# Sheet3.net
KiCad netlist of a schematic drawn in Altium Designer
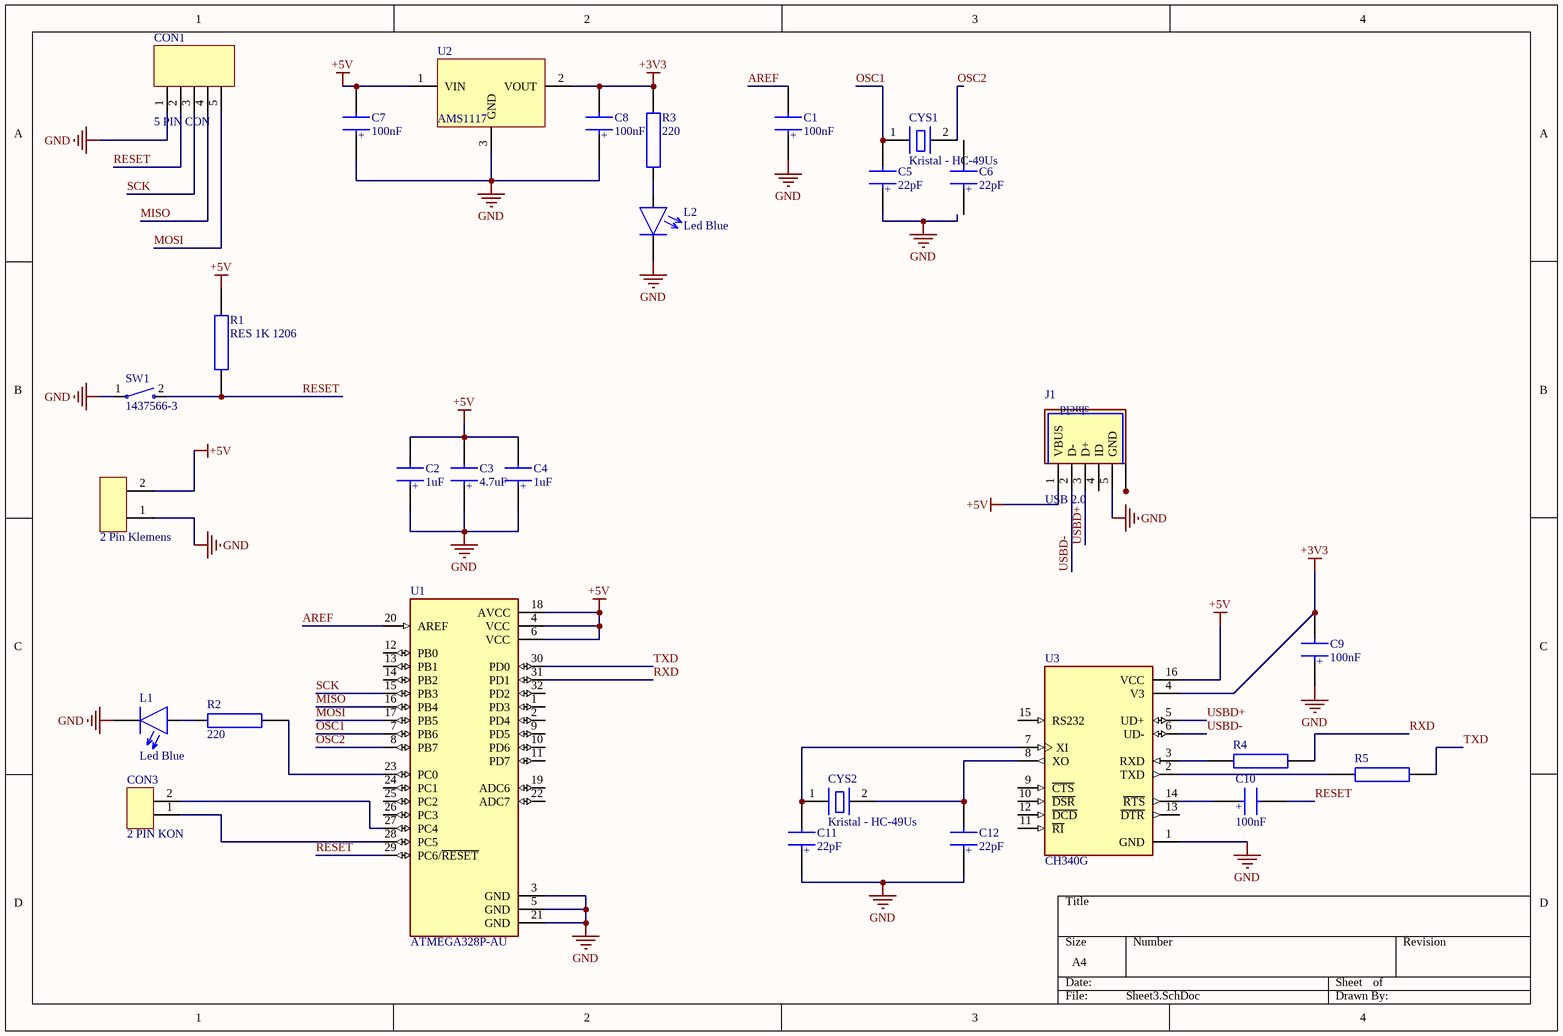
[diagram p0: Sheet3.SchDoc]

(export (version "E")
  (design (tool "Eeschema 10.0.6"))
  (components
    (comp (ref "C1")
      (value "100nF")
      (footprint "CAP_805")
      (description "0805 smd")
      (libsource (lib "Udemy_Schlib1") (part "CAP 22uf 0805"))
    )
    (comp (ref "C2")
      (value "1uF")
      (footprint "CAP_805")
      (description "0805 smd")
      (libsource (lib "Udemy_Schlib1") (part "CAP 22uf 0805"))
    )
    (comp (ref "C3")
      (value "4.7uF")
      (footprint "CAP_805")
      (description "0805 smd")
      (libsource (lib "Udemy_Schlib1") (part "CAP 22uf 0805"))
    )
    (comp (ref "C4")
      (value "1uF")
      (footprint "CAP_805")
      (description "0805 smd")
      (libsource (lib "Udemy_Schlib1") (part "CAP 22uf 0805"))
    )
    (comp (ref "C5")
      (value "22pF")
      (footprint "CAP_805")
      (description "0805 smd")
      (libsource (lib "Udemy_Schlib1") (part "CAP 22uf 0805"))
    )
    (comp (ref "C6")
      (value "22pF")
      (footprint "CAP_805")
      (description "0805 smd")
      (libsource (lib "Udemy_Schlib1") (part "CAP 22uf 0805"))
    )
    (comp (ref "C7")
      (value "100nF")
      (footprint "CAP_805")
      (description "0805 smd")
      (libsource (lib "Udemy_Schlib1") (part "CAP 22uf 0805"))
    )
    (comp (ref "C8")
      (value "100nF")
      (footprint "CAP_805")
      (description "0805 smd")
      (libsource (lib "Udemy_Schlib1") (part "CAP 22uf 0805"))
    )
    (comp (ref "C9")
      (value "100nF")
      (footprint "CAP_805")
      (description "0805 smd")
      (libsource (lib "Udemy_Schlib1") (part "CAP 22uf 0805"))
    )
    (comp (ref "C10")
      (value "100nF")
      (footprint "CAP_805")
      (description "0805 smd")
      (libsource (lib "Udemy_Schlib1") (part "CAP 22uf 0805"))
    )
    (comp (ref "C11")
      (value "22pF")
      (footprint "CAP_805")
      (description "0805 smd")
      (libsource (lib "Udemy_Schlib1") (part "CAP 22uf 0805"))
    )
    (comp (ref "C12")
      (value "22pF")
      (footprint "CAP_805")
      (description "0805 smd")
      (libsource (lib "Udemy_Schlib1") (part "CAP 22uf 0805"))
    )
    (comp (ref "CON1")
      (value "5 PIN CON")
      (footprint "5 PIN 2.54MM")
      (description "2.54mm vertical connector")
      (libsource (lib "Udemy_Schlib1") (part "5 PIN CON"))
    )
    (comp (ref "CON3")
      (value "2 PIN KON")
      (footprint "2 PIN 2.54MM")
      (description "2.54 mm vertical")
      (libsource (lib "Udemy_Schlib1") (part "2 PIN KON"))
    )
    (comp (ref "CYS1")
      (value "Kristal - HC-49Us")
      (footprint "Kristal - HC-49Us -smd")
      (description "Smd tipi kristal")
      (libsource (lib "Udemy_Schlib1") (part "Kristal - HC-49Us"))
    )
    (comp (ref "CYS2")
      (value "Kristal - HC-49Us")
      (footprint "Kristal - HC-49Us -smd")
      (description "Smd tipi kristal")
      (libsource (lib "Udemy_Schlib1") (part "Kristal - HC-49Us"))
    )
    (comp (ref "J1")
      (value "USB 2.0")
      (footprint "65100516121")
      (description "USB - mini B USB 2.0 Receptacle Connector 5 Position Surface Mount, Right Angle")
      (fields (field (name "MP") "65100516121") (field (name "MF") "WÃ¼rth Elektronik"))
      (libsource (lib "Schlib") (part "USB 2.0"))
    )
    (comp (ref "KLM1")
      (value "2 Pin Klemens")
      (footprint "5.08mm-2 pin")
      (description "5.08mm 2 pin klemens")
      (libsource (lib "Udemy_Schlib1") (part "2 Pin Klemens"))
    )
    (comp (ref "L1")
      (value "Led Blue")
      (footprint "Led 1206")
      (libsource (lib "Udemy_Schlib1") (part "Led Blue"))
    )
    (comp (ref "L2")
      (value "Led Blue")
      (footprint "Led 1206")
      (libsource (lib "Udemy_Schlib1") (part "Led Blue"))
    )
    (comp (ref "R1")
      (value "RES 1K 1206")
      (footprint "RES_1206")
      (libsource (lib "Udemy_Schlib1") (part "RES 1K 1206"))
    )
    (comp (ref "R2")
      (value "220")
      (footprint "RES_1206")
      (libsource (lib "Udemy_Schlib1") (part "RES 1K 1206"))
    )
    (comp (ref "R3")
      (value "220")
      (footprint "RES_1206")
      (libsource (lib "Udemy_Schlib1") (part "RES 1K 1206"))
    )
    (comp (ref "R4")
      (value "RES 1K 1206")
      (footprint "RES_1206")
      (libsource (lib "Udemy_Schlib1") (part "RES 1K 1206"))
    )
    (comp (ref "R5")
      (value "RES 1K 1206")
      (footprint "RES_1206")
      (libsource (lib "Udemy_Schlib1") (part "RES 1K 1206"))
    )
    (comp (ref "SW1")
      (value "1437566-3")
      (footprint "SW_1437566-3")
      (description "Switch Tactile OFF (ON) SPST Rectangular Button Gull Wing 0.05A 12VDC SMD Loose Piece")
      (libsource (lib "Schlib") (part "1437566-3"))
    )
    (comp (ref "U1")
      (value "ATMEGA328P-AU")
      (footprint "QFP80P900X900X120-32N")
      (description "AVR AVRÂ® ATmega Microcontroller IC 8-Bit 20MHz 32KB (16K x 16) FLASH 32-TQFP (7x7)")
      (fields (field (name "MF") "Microchip Technology"))
      (libsource (lib "Schlib") (part "ATMEGA328P-AU"))
    )
    (comp (ref "U2")
      (value "AMS1117")
      (footprint "AMS1117")
      (description "3V3 Voltage Regulator")
      (libsource (lib "Udemy_Schlib1") (part "AMS1117"))
    )
    (comp (ref "U3")
      (value "CH340G")
      (footprint "SOIC127P600X180-16N")
      (description "USB Interface Integrated Circuit")
      (fields (field (name "MP") "Ch340G") (field (name "MF") "WCH"))
      (libsource (lib "Schlib") (part "CH340G"))
    )
  )
  (nets
    (net (code "1") (name "+3V3") (class "Default")
      (node (ref "C8") (pin "2") (pinfunction "2_2") (pintype "passive"))
      (node (ref "C9") (pin "2") (pinfunction "2_2") (pintype "passive"))
      (node (ref "R3") (pin "2") (pintype "passive"))
      (node (ref "U2") (pin "2") (pinfunction "VOUT_2") (pintype "passive"))
      (node (ref "U3") (pin "4") (pinfunction "V3_4") (pintype "power_in"))
    )
    (net (code "2") (name "+5V") (class "Default")
      (node (ref "C2") (pin "2") (pinfunction "2_2") (pintype "passive"))
      (node (ref "C3") (pin "2") (pinfunction "2_2") (pintype "passive"))
      (node (ref "C4") (pin "2") (pinfunction "2_2") (pintype "passive"))
      (node (ref "C7") (pin "2") (pinfunction "2_2") (pintype "passive"))
      (node (ref "J1") (pin "1") (pinfunction "VBUS_1") (pintype "passive"))
      (node (ref "KLM1") (pin "2") (pintype "passive"))
      (node (ref "R1") (pin "2") (pintype "passive"))
      (node (ref "U1") (pin "18") (pinfunction "AVCC_18") (pintype "power_in"))
      (node (ref "U1") (pin "4") (pinfunction "VCC_4") (pintype "power_in"))
      (node (ref "U1") (pin "6") (pinfunction "VCC_6") (pintype "power_in"))
      (node (ref "U2") (pin "1") (pinfunction "VIN_1") (pintype "passive"))
      (node (ref "U3") (pin "16") (pinfunction "VCC_16") (pintype "power_in"))
    )
    (net (code "3") (name "/AREF") (class "Default")
      (node (ref "C1") (pin "2") (pinfunction "2_2") (pintype "passive"))
      (node (ref "U1") (pin "20") (pinfunction "AREF_20") (pintype "input"))
    )
    (net (code "4") (name "/MISO") (class "Default")
      (node (ref "CON1") (pin "4") (pintype "passive"))
      (node (ref "U1") (pin "16") (pinfunction "PB4_16") (pintype "bidirectional"))
    )
    (net (code "5") (name "/MOSI") (class "Default")
      (node (ref "CON1") (pin "5") (pintype "passive"))
      (node (ref "U1") (pin "17") (pinfunction "PB5_17") (pintype "bidirectional"))
    )
    (net (code "6") (name "/OSC1") (class "Default")
      (node (ref "C5") (pin "2") (pinfunction "2_2") (pintype "passive"))
      (node (ref "CYS1") (pin "1") (pintype "passive"))
      (node (ref "U1") (pin "7") (pinfunction "PB6_7") (pintype "bidirectional"))
    )
    (net (code "7") (name "/OSC2") (class "Default")
      (node (ref "CYS1") (pin "2") (pintype "passive"))
      (node (ref "U1") (pin "8") (pinfunction "PB7_8") (pintype "bidirectional"))
    )
    (net (code "8") (name "/RESET") (class "Default")
      (node (ref "C10") (pin "2") (pinfunction "2_2") (pintype "passive"))
      (node (ref "CON1") (pin "2") (pintype "passive"))
      (node (ref "R1") (pin "1") (pintype "passive"))
      (node (ref "SW1") (pin "2") (pinfunction "2_2") (pintype "passive"))
      (node (ref "U1") (pin "29") (pinfunction "PC6/~{RESET}_29") (pintype "bidirectional"))
    )
    (net (code "9") (name "/RXD") (class "Default")
      (node (ref "R4") (pin "2") (pintype "passive"))
      (node (ref "U1") (pin "31") (pinfunction "PD1_31") (pintype "bidirectional"))
    )
    (net (code "10") (name "/SCK") (class "Default")
      (node (ref "CON1") (pin "3") (pintype "passive"))
      (node (ref "U1") (pin "15") (pinfunction "PB3_15") (pintype "bidirectional"))
    )
    (net (code "11") (name "/TXD") (class "Default")
      (node (ref "R5") (pin "2") (pintype "passive"))
      (node (ref "U1") (pin "30") (pinfunction "PD0_30") (pintype "bidirectional"))
    )
    (net (code "12") (name "/USBD+") (class "Default")
      (node (ref "J1") (pin "3") (pinfunction "D+_3") (pintype "passive"))
      (node (ref "U3") (pin "5") (pinfunction "UD+_5") (pintype "bidirectional"))
    )
    (net (code "13") (name "/USBD-") (class "Default")
      (node (ref "J1") (pin "2") (pinfunction "D-_2") (pintype "passive"))
      (node (ref "U3") (pin "6") (pinfunction "UD-_6") (pintype "bidirectional"))
    )
    (net (code "14") (name "GND") (class "Default")
      (node (ref "C1") (pin "1") (pinfunction "1_1") (pintype "passive"))
      (node (ref "C11") (pin "1") (pinfunction "1_1") (pintype "passive"))
      (node (ref "C12") (pin "1") (pinfunction "1_1") (pintype "passive"))
      (node (ref "C2") (pin "1") (pinfunction "1_1") (pintype "passive"))
      (node (ref "C3") (pin "1") (pinfunction "1_1") (pintype "passive"))
      (node (ref "C4") (pin "1") (pinfunction "1_1") (pintype "passive"))
      (node (ref "C5") (pin "1") (pinfunction "1_1") (pintype "passive"))
      (node (ref "C7") (pin "1") (pinfunction "1_1") (pintype "passive"))
      (node (ref "C8") (pin "1") (pinfunction "1_1") (pintype "passive"))
      (node (ref "C9") (pin "1") (pinfunction "1_1") (pintype "passive"))
      (node (ref "CON1") (pin "1") (pintype "passive"))
      (node (ref "J1") (pin "5") (pinfunction "GND_5") (pintype "passive"))
      (node (ref "KLM1") (pin "1") (pintype "passive"))
      (node (ref "L1") (pin "2") (pintype "passive"))
      (node (ref "L2") (pin "2") (pintype "passive"))
      (node (ref "SW1") (pin "1") (pinfunction "1_1") (pintype "passive"))
      (node (ref "U1") (pin "21") (pinfunction "GND_21") (pintype "power_in"))
      (node (ref "U1") (pin "3") (pinfunction "GND_3") (pintype "power_in"))
      (node (ref "U1") (pin "5") (pinfunction "GND_5") (pintype "power_in"))
      (node (ref "U2") (pin "3") (pinfunction "GND_3") (pintype "passive"))
      (node (ref "U3") (pin "1") (pinfunction "GND_1") (pintype "power_in"))
    )
    (net (code "15") (name "Net-(J1-SHIELD-PadS1)") (class "Default")
      (node (ref "J1") (pin "S1") (pinfunction "SHIELD_S1") (pintype "passive"))
      (node (ref "J1") (pin "S2") (pinfunction "SHIELD_S2") (pintype "passive"))
      (node (ref "J1") (pin "S3") (pinfunction "SHIELD_S3") (pintype "passive"))
      (node (ref "J1") (pin "S4") (pinfunction "SHIELD_S4") (pintype "passive"))
    )
    (net (code "16") (name "Net-(L1-Pad1)") (class "Default")
      (node (ref "L1") (pin "1") (pintype "passive"))
      (node (ref "R2") (pin "1") (pintype "passive"))
    )
    (net (code "17") (name "Net-(L2-Pad1)") (class "Default")
      (node (ref "L2") (pin "1") (pintype "passive"))
      (node (ref "R3") (pin "1") (pintype "passive"))
    )
    (net (code "18") (name "Net-(U1-PC0)") (class "Default")
      (node (ref "R2") (pin "2") (pintype "passive"))
      (node (ref "U1") (pin "23") (pinfunction "PC0_23") (pintype "bidirectional"))
    )
    (net (code "19") (name "Net-(U1-PC4)") (class "Default")
      (node (ref "CON3") (pin "2") (pintype "passive"))
      (node (ref "U1") (pin "27") (pinfunction "PC4_27") (pintype "bidirectional"))
    )
    (net (code "20") (name "Net-(U1-PC5)") (class "Default")
      (node (ref "CON3") (pin "1") (pintype "passive"))
      (node (ref "U1") (pin "28") (pinfunction "PC5_28") (pintype "bidirectional"))
    )
    (net (code "21") (name "Net-(U3-RXD)") (class "Default")
      (node (ref "R4") (pin "1") (pintype "passive"))
      (node (ref "U3") (pin "3") (pinfunction "RXD_3") (pintype "input"))
    )
    (net (code "22") (name "Net-(U3-TXD)") (class "Default")
      (node (ref "R5") (pin "1") (pintype "passive"))
      (node (ref "U3") (pin "2") (pinfunction "TXD_2") (pintype "output"))
    )
    (net (code "23") (name "Net-(U3-XI)") (class "Default")
      (node (ref "C11") (pin "2") (pinfunction "2_2") (pintype "passive"))
      (node (ref "CYS2") (pin "1") (pintype "passive"))
      (node (ref "U3") (pin "7") (pinfunction "XI_7") (pintype "input"))
    )
    (net (code "24") (name "Net-(U3-XO)") (class "Default")
      (node (ref "C12") (pin "2") (pinfunction "2_2") (pintype "passive"))
      (node (ref "CYS2") (pin "2") (pintype "passive"))
      (node (ref "U3") (pin "8") (pinfunction "XO_8") (pintype "output"))
    )
    (net (code "25") (name "Net-(U3-~{RTS})") (class "Default")
      (node (ref "C10") (pin "1") (pinfunction "1_1") (pintype "passive"))
      (node (ref "U3") (pin "14") (pinfunction "~{RTS}_14") (pintype "output"))
    )
    (net (code "26") (name "unconnected-(C6-Pad1)") (class "Default")
      (node (ref "C6") (pin "1") (pinfunction "1_1") (pintype "passive"))
    )
    (net (code "27") (name "unconnected-(C6-Pad2)") (class "Default")
      (node (ref "C6") (pin "2") (pinfunction "2_2") (pintype "passive"))
    )
    (net (code "28") (name "unconnected-(J1-ID-Pad4)") (class "Default")
      (node (ref "J1") (pin "4") (pinfunction "ID_4") (pintype "passive"))
    )
    (net (code "29") (name "unconnected-(U1-ADC6-Pad19)") (class "Default")
      (node (ref "U1") (pin "19") (pinfunction "ADC6_19") (pintype "bidirectional"))
    )
    (net (code "30") (name "unconnected-(U1-ADC7-Pad22)") (class "Default")
      (node (ref "U1") (pin "22") (pinfunction "ADC7_22") (pintype "bidirectional"))
    )
    (net (code "31") (name "unconnected-(U1-PB0-Pad12)") (class "Default")
      (node (ref "U1") (pin "12") (pinfunction "PB0_12") (pintype "bidirectional"))
    )
    (net (code "32") (name "unconnected-(U1-PB1-Pad13)") (class "Default")
      (node (ref "U1") (pin "13") (pinfunction "PB1_13") (pintype "bidirectional"))
    )
    (net (code "33") (name "unconnected-(U1-PB2-Pad14)") (class "Default")
      (node (ref "U1") (pin "14") (pinfunction "PB2_14") (pintype "bidirectional"))
    )
    (net (code "34") (name "unconnected-(U1-PC1-Pad24)") (class "Default")
      (node (ref "U1") (pin "24") (pinfunction "PC1_24") (pintype "bidirectional"))
    )
    (net (code "35") (name "unconnected-(U1-PC2-Pad25)") (class "Default")
      (node (ref "U1") (pin "25") (pinfunction "PC2_25") (pintype "bidirectional"))
    )
    (net (code "36") (name "unconnected-(U1-PC3-Pad26)") (class "Default")
      (node (ref "U1") (pin "26") (pinfunction "PC3_26") (pintype "bidirectional"))
    )
    (net (code "37") (name "unconnected-(U1-PD2-Pad32)") (class "Default")
      (node (ref "U1") (pin "32") (pinfunction "PD2_32") (pintype "bidirectional"))
    )
    (net (code "38") (name "unconnected-(U1-PD3-Pad1)") (class "Default")
      (node (ref "U1") (pin "1") (pinfunction "PD3_1") (pintype "bidirectional"))
    )
    (net (code "39") (name "unconnected-(U1-PD4-Pad2)") (class "Default")
      (node (ref "U1") (pin "2") (pinfunction "PD4_2") (pintype "bidirectional"))
    )
    (net (code "40") (name "unconnected-(U1-PD5-Pad9)") (class "Default")
      (node (ref "U1") (pin "9") (pinfunction "PD5_9") (pintype "bidirectional"))
    )
    (net (code "41") (name "unconnected-(U1-PD6-Pad10)") (class "Default")
      (node (ref "U1") (pin "10") (pinfunction "PD6_10") (pintype "bidirectional"))
    )
    (net (code "42") (name "unconnected-(U1-PD7-Pad11)") (class "Default")
      (node (ref "U1") (pin "11") (pinfunction "PD7_11") (pintype "bidirectional"))
    )
    (net (code "43") (name "unconnected-(U3-RS232-Pad15)") (class "Default")
      (node (ref "U3") (pin "15") (pinfunction "RS232_15") (pintype "input"))
    )
    (net (code "44") (name "unconnected-(U3-~{CTS}-Pad9)") (class "Default")
      (node (ref "U3") (pin "9") (pinfunction "~{CTS}_9") (pintype "input"))
    )
    (net (code "45") (name "unconnected-(U3-~{DCD}-Pad12)") (class "Default")
      (node (ref "U3") (pin "12") (pinfunction "~{DCD}_12") (pintype "input"))
    )
    (net (code "46") (name "unconnected-(U3-~{DSR}-Pad10)") (class "Default")
      (node (ref "U3") (pin "10") (pinfunction "~{DSR}_10") (pintype "input"))
    )
    (net (code "47") (name "unconnected-(U3-~{DTR}-Pad13)") (class "Default")
      (node (ref "U3") (pin "13") (pinfunction "~{DTR}_13") (pintype "output"))
    )
    (net (code "48") (name "unconnected-(U3-~{RI}-Pad11)") (class "Default")
      (node (ref "U3") (pin "11") (pinfunction "~{RI}_11") (pintype "input"))
    )
  )
)
